# vu.net
KiCad netlist of a schematic drawn in EAGLE
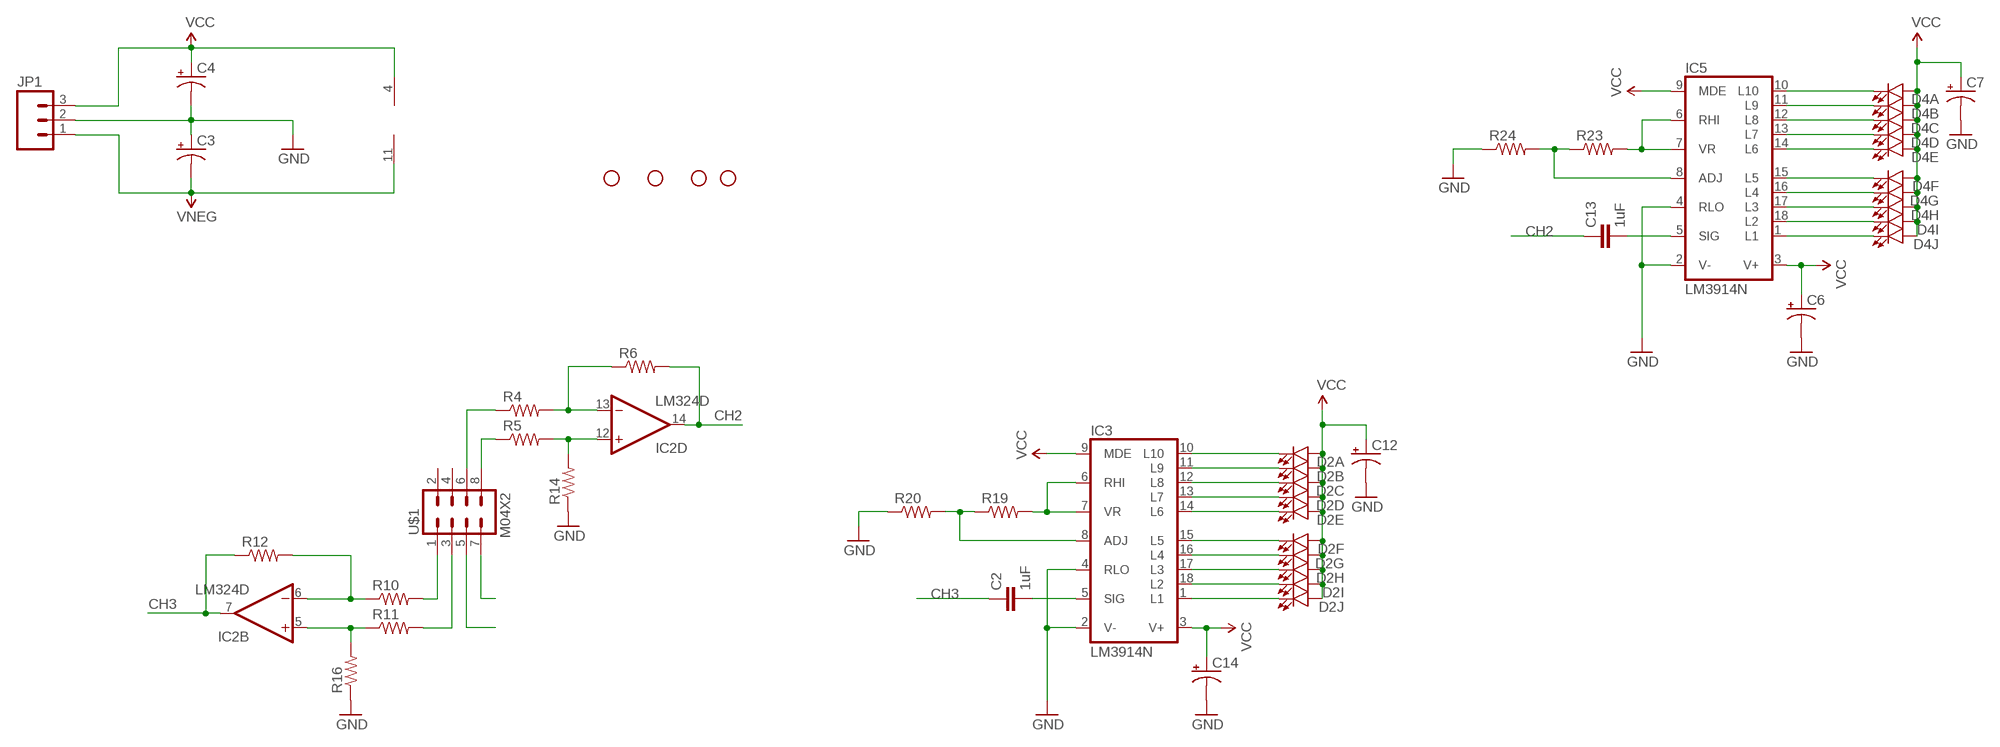
[diagram p0: schematic, sheet 1]

(export (version "E")
  (design (tool "Eeschema 10.0.6"))
  (components
    (comp (ref "C2")
      (value "1uF")
      (footprint "eagle-import:1206")
      (libsource (lib "eagle-import") (part "CAP1206"))
    )
    (comp (ref "C3")
      (value "CAP_POLPTH1")
      (footprint "eagle-import:CPOL-RADIAL-100UF-25V")
      (libsource (lib "eagle-import") (part "CAP_POLPTH1"))
    )
    (comp (ref "C4")
      (value "CAP_POLPTH1")
      (footprint "eagle-import:CPOL-RADIAL-100UF-25V")
      (libsource (lib "eagle-import") (part "CAP_POLPTH1"))
    )
    (comp (ref "C6")
      (value "CAP_POL1206")
      (footprint "eagle-import:EIA3216")
      (libsource (lib "eagle-import") (part "CAP_POL1206"))
    )
    (comp (ref "C7")
      (value "CAP_POL1206")
      (footprint "eagle-import:EIA3216")
      (libsource (lib "eagle-import") (part "CAP_POL1206"))
    )
    (comp (ref "C12")
      (value "CAP_POL1206")
      (footprint "eagle-import:EIA3216")
      (libsource (lib "eagle-import") (part "CAP_POL1206"))
    )
    (comp (ref "C13")
      (value "1uF")
      (footprint "eagle-import:1206")
      (libsource (lib "eagle-import") (part "CAP1206"))
    )
    (comp (ref "C14")
      (value "CAP_POL1206")
      (footprint "eagle-import:EIA3216")
      (libsource (lib "eagle-import") (part "CAP_POL1206"))
    )
    (comp (ref "D2")
      (value "LED_BARGRAPH_10")
      (footprint "eagle-import:LED_BARGAPH_10")
      (libsource (lib "eagle-import") (part "LED_BARGRAPH_10"))
    )
    (comp (ref "D4")
      (value "LED_BARGRAPH_10")
      (footprint "eagle-import:LED_BARGAPH_10")
      (libsource (lib "eagle-import") (part "LED_BARGRAPH_10"))
    )
    (comp (ref "IC2")
      (value "LM324D")
      (footprint "eagle-import:SO14")
      (libsource (lib "eagle-import") (part "LM324D"))
    )
    (comp (ref "IC3")
      (value "LM3914N")
      (footprint "eagle-import:DIL18")
      (libsource (lib "eagle-import") (part "LM3914N"))
    )
    (comp (ref "IC5")
      (value "LM3914N")
      (footprint "eagle-import:DIL18")
      (libsource (lib "eagle-import") (part "LM3914N"))
    )
    (comp (ref "JP1")
      (value "M03POLAR")
      (footprint "eagle-import:MOLEX-1X3")
      (libsource (lib "eagle-import") (part "M03POLAR"))
    )
    (comp (ref "R4")
      (value "RESISTOR0603")
      (footprint "eagle-import:0603-RES")
      (libsource (lib "eagle-import") (part "RESISTOR0603"))
    )
    (comp (ref "R5")
      (value "RESISTOR0603")
      (footprint "eagle-import:0603-RES")
      (libsource (lib "eagle-import") (part "RESISTOR0603"))
    )
    (comp (ref "R6")
      (value "RESISTOR0603")
      (footprint "eagle-import:0603-RES")
      (libsource (lib "eagle-import") (part "RESISTOR0603"))
    )
    (comp (ref "R10")
      (value "RESISTOR0603")
      (footprint "eagle-import:0603-RES")
      (libsource (lib "eagle-import") (part "RESISTOR0603"))
    )
    (comp (ref "R11")
      (value "RESISTOR0603")
      (footprint "eagle-import:0603-RES")
      (libsource (lib "eagle-import") (part "RESISTOR0603"))
    )
    (comp (ref "R12")
      (value "RESISTOR0603")
      (footprint "eagle-import:0603-RES")
      (libsource (lib "eagle-import") (part "RESISTOR0603"))
    )
    (comp (ref "R14")
      (value "RESISTOR0603")
      (footprint "eagle-import:0603-RES")
      (libsource (lib "eagle-import") (part "RESISTOR0603"))
    )
    (comp (ref "R16")
      (value "RESISTOR0603")
      (footprint "eagle-import:0603-RES")
      (libsource (lib "eagle-import") (part "RESISTOR0603"))
    )
    (comp (ref "R19")
      (value "RESISTOR1206")
      (footprint "eagle-import:1206")
      (libsource (lib "eagle-import") (part "RESISTOR1206"))
    )
    (comp (ref "R20")
      (value "RESISTOR1206")
      (footprint "eagle-import:1206")
      (libsource (lib "eagle-import") (part "RESISTOR1206"))
    )
    (comp (ref "R23")
      (value "RESISTOR1206")
      (footprint "eagle-import:1206")
      (libsource (lib "eagle-import") (part "RESISTOR1206"))
    )
    (comp (ref "R24")
      (value "RESISTOR1206")
      (footprint "eagle-import:1206")
      (libsource (lib "eagle-import") (part "RESISTOR1206"))
    )
    (comp (ref "STANDOFF1")
      (value "STAND-OFF")
      (footprint "eagle-import:STAND-OFF")
      (libsource (lib "eagle-import") (part "STAND-OFF"))
    )
    (comp (ref "STANDOFF2")
      (value "STAND-OFF")
      (footprint "eagle-import:STAND-OFF")
      (libsource (lib "eagle-import") (part "STAND-OFF"))
    )
    (comp (ref "STANDOFF3")
      (value "STAND-OFF")
      (footprint "eagle-import:STAND-OFF")
      (libsource (lib "eagle-import") (part "STAND-OFF"))
    )
    (comp (ref "STANDOFF4")
      (value "STAND-OFF")
      (footprint "eagle-import:STAND-OFF")
      (libsource (lib "eagle-import") (part "STAND-OFF"))
    )
    (comp (ref "U$1")
      (value "M04X2")
      (footprint "eagle-import:2X4")
      (libsource (lib "eagle-import") (part "M04X2"))
    )
  )
  (nets
    (net (code "1") (name "/CH2") (class "Default")
      (node (ref "C13") (pin "1") (pinfunction "1_1") (pintype "passive"))
      (node (ref "IC2") (pin "14") (pinfunction "OUT_14") (pintype "output"))
      (node (ref "R6") (pin "2") (pinfunction "2_2") (pintype "passive"))
    )
    (net (code "2") (name "/CH3") (class "Default")
      (node (ref "C2") (pin "1") (pinfunction "1_1") (pintype "passive"))
      (node (ref "IC2") (pin "7") (pinfunction "OUT_7") (pintype "output"))
      (node (ref "R12") (pin "1") (pinfunction "1_1") (pintype "passive"))
    )
    (net (code "3") (name "GND") (class "Default")
      (node (ref "C12") (pin "C") (pinfunction "-_C") (pintype "passive"))
      (node (ref "C14") (pin "C") (pinfunction "-_C") (pintype "passive"))
      (node (ref "C3") (pin "1") (pinfunction "+_1") (pintype "passive"))
      (node (ref "C4") (pin "2") (pinfunction "-_2") (pintype "passive"))
      (node (ref "C6") (pin "C") (pinfunction "-_C") (pintype "passive"))
      (node (ref "C7") (pin "C") (pinfunction "-_C") (pintype "passive"))
      (node (ref "IC3") (pin "2") (pinfunction "V-_2") (pintype "power_in"))
      (node (ref "IC3") (pin "4") (pinfunction "RLO_4") (pintype "input"))
      (node (ref "IC5") (pin "2") (pinfunction "V-_2") (pintype "power_in"))
      (node (ref "IC5") (pin "4") (pinfunction "RLO_4") (pintype "input"))
      (node (ref "JP1") (pin "2") (pinfunction "2_2") (pintype "passive"))
      (node (ref "R14") (pin "1") (pinfunction "1_1") (pintype "passive"))
      (node (ref "R16") (pin "1") (pinfunction "1_1") (pintype "passive"))
      (node (ref "R20") (pin "1") (pinfunction "1_1") (pintype "passive"))
      (node (ref "R24") (pin "1") (pinfunction "1_1") (pintype "passive"))
    )
    (net (code "4") (name "Net-(D2A-C)") (class "Default")
      (node (ref "D2") (pin "20") (pinfunction "C_20") (pintype "passive"))
      (node (ref "IC3") (pin "10") (pinfunction "L10_10") (pintype "output"))
    )
    (net (code "5") (name "Net-(D2B-C)") (class "Default")
      (node (ref "D2") (pin "19") (pinfunction "C_19") (pintype "passive"))
      (node (ref "IC3") (pin "11") (pinfunction "L9_11") (pintype "output"))
    )
    (net (code "6") (name "Net-(D2C-C)") (class "Default")
      (node (ref "D2") (pin "18") (pinfunction "C_18") (pintype "passive"))
      (node (ref "IC3") (pin "12") (pinfunction "L8_12") (pintype "output"))
    )
    (net (code "7") (name "Net-(D2D-C)") (class "Default")
      (node (ref "D2") (pin "17") (pinfunction "C_17") (pintype "passive"))
      (node (ref "IC3") (pin "13") (pinfunction "L7_13") (pintype "output"))
    )
    (net (code "8") (name "Net-(D2E-C)") (class "Default")
      (node (ref "D2") (pin "16") (pinfunction "C_16") (pintype "passive"))
      (node (ref "IC3") (pin "14") (pinfunction "L6_14") (pintype "output"))
    )
    (net (code "9") (name "Net-(D2F-C)") (class "Default")
      (node (ref "D2") (pin "15") (pinfunction "C_15") (pintype "passive"))
      (node (ref "IC3") (pin "15") (pinfunction "L5_15") (pintype "output"))
    )
    (net (code "10") (name "Net-(D2G-C)") (class "Default")
      (node (ref "D2") (pin "14") (pinfunction "C_14") (pintype "passive"))
      (node (ref "IC3") (pin "16") (pinfunction "L4_16") (pintype "output"))
    )
    (net (code "11") (name "Net-(D2H-C)") (class "Default")
      (node (ref "D2") (pin "13") (pinfunction "C_13") (pintype "passive"))
      (node (ref "IC3") (pin "17") (pinfunction "L3_17") (pintype "output"))
    )
    (net (code "12") (name "Net-(D2I-C)") (class "Default")
      (node (ref "D2") (pin "12") (pinfunction "C_12") (pintype "passive"))
      (node (ref "IC3") (pin "18") (pinfunction "L2_18") (pintype "output"))
    )
    (net (code "13") (name "Net-(D2J-C)") (class "Default")
      (node (ref "D2") (pin "11") (pinfunction "C_11") (pintype "passive"))
      (node (ref "IC3") (pin "1") (pinfunction "L1_1") (pintype "output"))
    )
    (net (code "14") (name "Net-(D4A-C)") (class "Default")
      (node (ref "D4") (pin "20") (pinfunction "C_20") (pintype "passive"))
      (node (ref "IC5") (pin "10") (pinfunction "L10_10") (pintype "output"))
    )
    (net (code "15") (name "Net-(D4B-C)") (class "Default")
      (node (ref "D4") (pin "19") (pinfunction "C_19") (pintype "passive"))
      (node (ref "IC5") (pin "11") (pinfunction "L9_11") (pintype "output"))
    )
    (net (code "16") (name "Net-(D4C-C)") (class "Default")
      (node (ref "D4") (pin "18") (pinfunction "C_18") (pintype "passive"))
      (node (ref "IC5") (pin "12") (pinfunction "L8_12") (pintype "output"))
    )
    (net (code "17") (name "Net-(D4D-C)") (class "Default")
      (node (ref "D4") (pin "17") (pinfunction "C_17") (pintype "passive"))
      (node (ref "IC5") (pin "13") (pinfunction "L7_13") (pintype "output"))
    )
    (net (code "18") (name "Net-(D4E-C)") (class "Default")
      (node (ref "D4") (pin "16") (pinfunction "C_16") (pintype "passive"))
      (node (ref "IC5") (pin "14") (pinfunction "L6_14") (pintype "output"))
    )
    (net (code "19") (name "Net-(D4F-C)") (class "Default")
      (node (ref "D4") (pin "15") (pinfunction "C_15") (pintype "passive"))
      (node (ref "IC5") (pin "15") (pinfunction "L5_15") (pintype "output"))
    )
    (net (code "20") (name "Net-(D4G-C)") (class "Default")
      (node (ref "D4") (pin "14") (pinfunction "C_14") (pintype "passive"))
      (node (ref "IC5") (pin "16") (pinfunction "L4_16") (pintype "output"))
    )
    (net (code "21") (name "Net-(D4H-C)") (class "Default")
      (node (ref "D4") (pin "13") (pinfunction "C_13") (pintype "passive"))
      (node (ref "IC5") (pin "17") (pinfunction "L3_17") (pintype "output"))
    )
    (net (code "22") (name "Net-(D4I-C)") (class "Default")
      (node (ref "D4") (pin "12") (pinfunction "C_12") (pintype "passive"))
      (node (ref "IC5") (pin "18") (pinfunction "L2_18") (pintype "output"))
    )
    (net (code "23") (name "Net-(D4J-C)") (class "Default")
      (node (ref "D4") (pin "11") (pinfunction "C_11") (pintype "passive"))
      (node (ref "IC5") (pin "1") (pinfunction "L1_1") (pintype "output"))
    )
    (net (code "24") (name "Net-(IC2B-+IN)") (class "Default")
      (node (ref "IC2") (pin "5") (pinfunction "+IN_5") (pintype "input"))
      (node (ref "R11") (pin "1") (pinfunction "1_1") (pintype "passive"))
      (node (ref "R16") (pin "2") (pinfunction "2_2") (pintype "passive"))
    )
    (net (code "25") (name "Net-(IC2B--IN)") (class "Default")
      (node (ref "IC2") (pin "6") (pinfunction "-IN_6") (pintype "input"))
      (node (ref "R10") (pin "1") (pinfunction "1_1") (pintype "passive"))
      (node (ref "R12") (pin "2") (pinfunction "2_2") (pintype "passive"))
    )
    (net (code "26") (name "Net-(IC2D-+IN)") (class "Default")
      (node (ref "IC2") (pin "12") (pinfunction "+IN_12") (pintype "input"))
      (node (ref "R14") (pin "2") (pinfunction "2_2") (pintype "passive"))
      (node (ref "R5") (pin "2") (pinfunction "2_2") (pintype "passive"))
    )
    (net (code "27") (name "Net-(IC2D--IN)") (class "Default")
      (node (ref "IC2") (pin "13") (pinfunction "-IN_13") (pintype "input"))
      (node (ref "R4") (pin "2") (pinfunction "2_2") (pintype "passive"))
      (node (ref "R6") (pin "1") (pinfunction "1_1") (pintype "passive"))
    )
    (net (code "28") (name "Net-(IC3-ADJ)") (class "Default")
      (node (ref "IC3") (pin "8") (pinfunction "ADJ_8") (pintype "input"))
      (node (ref "R19") (pin "1") (pinfunction "1_1") (pintype "passive"))
      (node (ref "R20") (pin "2") (pinfunction "2_2") (pintype "passive"))
    )
    (net (code "29") (name "Net-(IC3-RHI)") (class "Default")
      (node (ref "IC3") (pin "6") (pinfunction "RHI_6") (pintype "input"))
      (node (ref "IC3") (pin "7") (pinfunction "VR_7") (pintype "output"))
      (node (ref "R19") (pin "2") (pinfunction "2_2") (pintype "passive"))
    )
    (net (code "30") (name "Net-(IC3-SIG)") (class "Default")
      (node (ref "C2") (pin "2") (pinfunction "2_2") (pintype "passive"))
      (node (ref "IC3") (pin "5") (pinfunction "SIG_5") (pintype "input"))
    )
    (net (code "31") (name "Net-(IC5-ADJ)") (class "Default")
      (node (ref "IC5") (pin "8") (pinfunction "ADJ_8") (pintype "input"))
      (node (ref "R23") (pin "1") (pinfunction "1_1") (pintype "passive"))
      (node (ref "R24") (pin "2") (pinfunction "2_2") (pintype "passive"))
    )
    (net (code "32") (name "Net-(IC5-RHI)") (class "Default")
      (node (ref "IC5") (pin "6") (pinfunction "RHI_6") (pintype "input"))
      (node (ref "IC5") (pin "7") (pinfunction "VR_7") (pintype "output"))
      (node (ref "R23") (pin "2") (pinfunction "2_2") (pintype "passive"))
    )
    (net (code "33") (name "Net-(IC5-SIG)") (class "Default")
      (node (ref "C13") (pin "2") (pinfunction "2_2") (pintype "passive"))
      (node (ref "IC5") (pin "5") (pinfunction "SIG_5") (pintype "input"))
    )
    (net (code "34") (name "Net-(R4-Pad1)") (class "Default")
      (node (ref "R4") (pin "1") (pinfunction "1_1") (pintype "passive"))
      (node (ref "U$1") (pin "6") (pinfunction "6_6") (pintype "passive"))
    )
    (net (code "35") (name "Net-(R5-Pad1)") (class "Default")
      (node (ref "R5") (pin "1") (pinfunction "1_1") (pintype "passive"))
      (node (ref "U$1") (pin "8") (pinfunction "8_8") (pintype "passive"))
    )
    (net (code "36") (name "Net-(R10-Pad2)") (class "Default")
      (node (ref "R10") (pin "2") (pinfunction "2_2") (pintype "passive"))
      (node (ref "U$1") (pin "1") (pinfunction "1_1") (pintype "passive"))
    )
    (net (code "37") (name "Net-(R11-Pad2)") (class "Default")
      (node (ref "R11") (pin "2") (pinfunction "2_2") (pintype "passive"))
      (node (ref "U$1") (pin "3") (pinfunction "3_3") (pintype "passive"))
    )
    (net (code "38") (name "VCC") (class "Default")
      (node (ref "C12") (pin "A") (pinfunction "+_A") (pintype "passive"))
      (node (ref "C14") (pin "A") (pinfunction "+_A") (pintype "passive"))
      (node (ref "C4") (pin "1") (pinfunction "+_1") (pintype "passive"))
      (node (ref "C6") (pin "A") (pinfunction "+_A") (pintype "passive"))
      (node (ref "C7") (pin "A") (pinfunction "+_A") (pintype "passive"))
      (node (ref "D2") (pin "1") (pinfunction "A_1") (pintype "passive"))
      (node (ref "D2") (pin "10") (pinfunction "A_10") (pintype "passive"))
      (node (ref "D2") (pin "2") (pinfunction "A_2") (pintype "passive"))
      (node (ref "D2") (pin "3") (pinfunction "A_3") (pintype "passive"))
      (node (ref "D2") (pin "4") (pinfunction "A_4") (pintype "passive"))
      (node (ref "D2") (pin "5") (pinfunction "A_5") (pintype "passive"))
      (node (ref "D2") (pin "6") (pinfunction "A_6") (pintype "passive"))
      (node (ref "D2") (pin "7") (pinfunction "A_7") (pintype "passive"))
      (node (ref "D2") (pin "8") (pinfunction "A_8") (pintype "passive"))
      (node (ref "D2") (pin "9") (pinfunction "A_9") (pintype "passive"))
      (node (ref "D4") (pin "1") (pinfunction "A_1") (pintype "passive"))
      (node (ref "D4") (pin "10") (pinfunction "A_10") (pintype "passive"))
      (node (ref "D4") (pin "2") (pinfunction "A_2") (pintype "passive"))
      (node (ref "D4") (pin "3") (pinfunction "A_3") (pintype "passive"))
      (node (ref "D4") (pin "4") (pinfunction "A_4") (pintype "passive"))
      (node (ref "D4") (pin "5") (pinfunction "A_5") (pintype "passive"))
      (node (ref "D4") (pin "6") (pinfunction "A_6") (pintype "passive"))
      (node (ref "D4") (pin "7") (pinfunction "A_7") (pintype "passive"))
      (node (ref "D4") (pin "8") (pinfunction "A_8") (pintype "passive"))
      (node (ref "D4") (pin "9") (pinfunction "A_9") (pintype "passive"))
      (node (ref "IC2") (pin "4") (pinfunction "V+_4") (pintype "power_in"))
      (node (ref "IC3") (pin "3") (pinfunction "V+_3") (pintype "power_in"))
      (node (ref "IC3") (pin "9") (pinfunction "MDE_9") (pintype "input"))
      (node (ref "IC5") (pin "3") (pinfunction "V+_3") (pintype "power_in"))
      (node (ref "IC5") (pin "9") (pinfunction "MDE_9") (pintype "input"))
      (node (ref "JP1") (pin "3") (pinfunction "3_3") (pintype "passive"))
    )
    (net (code "39") (name "VNEG") (class "Default")
      (node (ref "C3") (pin "2") (pinfunction "-_2") (pintype "passive"))
      (node (ref "IC2") (pin "11") (pinfunction "V-_11") (pintype "power_in"))
      (node (ref "JP1") (pin "1") (pinfunction "1_1") (pintype "passive"))
    )
    (net (code "40") (name "unconnected-(U$1-Pad2)") (class "Default")
      (node (ref "U$1") (pin "2") (pinfunction "2_2") (pintype "passive"))
    )
    (net (code "41") (name "unconnected-(U$1-Pad4)") (class "Default")
      (node (ref "U$1") (pin "4") (pinfunction "4_4") (pintype "passive"))
    )
    (net (code "42") (name "unconnected-(U$1-Pad5)") (class "Default")
      (node (ref "U$1") (pin "5") (pinfunction "5_5") (pintype "passive"))
    )
    (net (code "43") (name "unconnected-(U$1-Pad7)") (class "Default")
      (node (ref "U$1") (pin "7") (pinfunction "7_7") (pintype "passive"))
    )
  )
)
